# MonitorAmp.net
KiCad netlist of a schematic drawn in Altium Designer
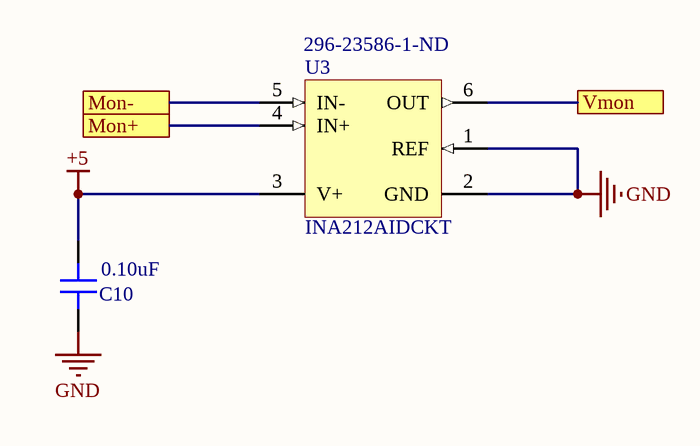
[diagram p0: MonitorAmp.SchDoc]

(export (version "E")
  (design (tool "Eeschema 10.0.6"))
  (components
    (comp (ref "C10")
      (value "0.10uF")
      (footprint "CAP 0402/1005")
      (description "CAP CER 0.1UF 16V X7R 0402")
      (fields
        (field (name "PART NUMBER") "GRM155R71C104JA88D")
        (field (name "MANUFACTURER") "Murata Electronics North America")
      )
      (libsource (lib "Celestial Library Database") (part "Capacitor"))
    )
    (comp (ref "U3")
      (value "INA212AIDCKT")
      (footprint "DCK0006A_L")
      (fields
        (field (name "MANUFACTURER") "TexasInstruments")
        (field (name "SUPPLIER PART NUMBER 1") "296-23586-1-ND")
      )
      (libsource (lib "Altium Content Vault") (part "TI-INA21X_199A-DCK-6"))
    )
  )
  (nets
    (net (code "1") (name "+5") (class "Default")
      (node (ref "C10") (pin "2") (pinfunction "2_2") (pintype "passive"))
      (node (ref "U3") (pin "3") (pinfunction "V+_3") (pintype "power_in"))
    )
    (net (code "2") (name "/Mon+") (class "Default")
      (node (ref "U3") (pin "4") (pinfunction "IN+_4") (pintype "input"))
    )
    (net (code "3") (name "/Mon-") (class "Default")
      (node (ref "U3") (pin "5") (pinfunction "IN-_5") (pintype "input"))
    )
    (net (code "4") (name "/Vmon") (class "Default")
      (node (ref "U3") (pin "6") (pinfunction "OUT_6") (pintype "output"))
    )
    (net (code "5") (name "GND") (class "Default")
      (node (ref "C10") (pin "1") (pinfunction "1_1") (pintype "passive"))
      (node (ref "U3") (pin "1") (pinfunction "REF_1") (pintype "input"))
      (node (ref "U3") (pin "2") (pinfunction "GND_2") (pintype "power_in"))
    )
  )
)
